# stepper_driver.net
KiCad netlist of a schematic drawn in EAGLE
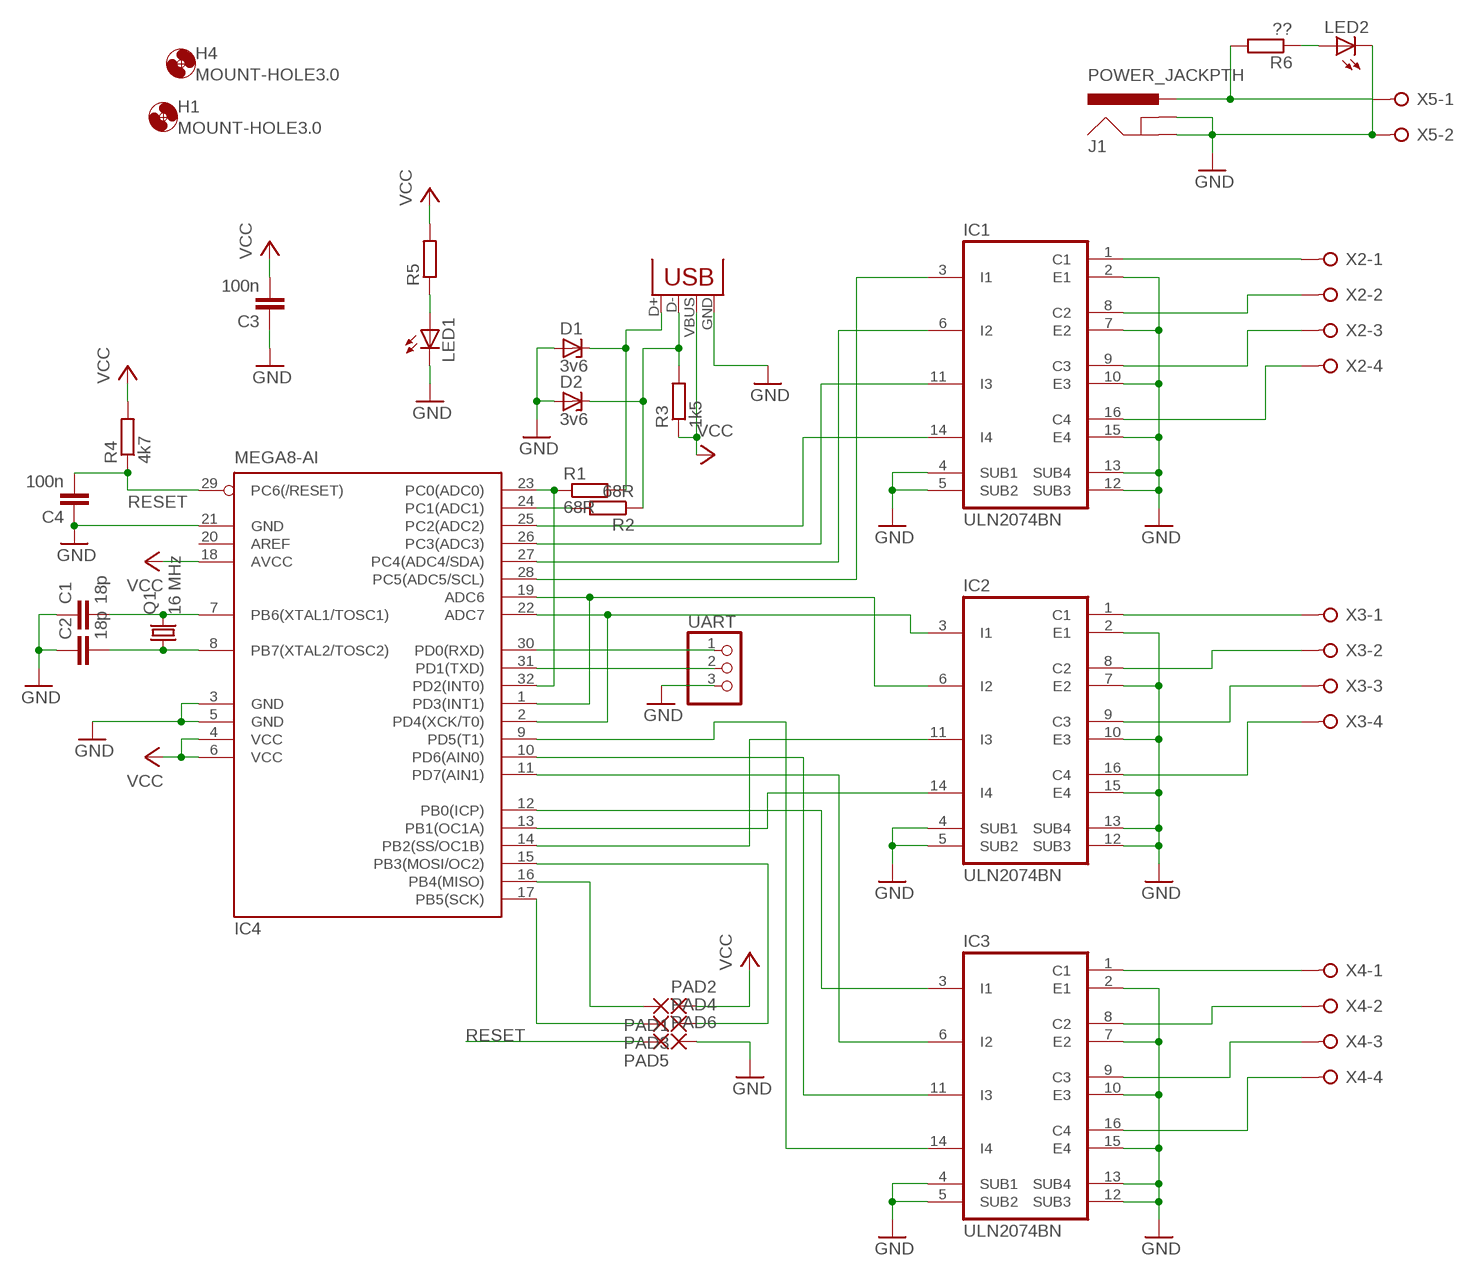
[diagram p0: schematic, sheet 1]

(export (version "E")
  (design (tool "Eeschema 10.0.6"))
  (components
    (comp (ref "C1")
      (value "18p")
      (footprint "eagle-import:C025-025X050")
      (libsource (lib "eagle-import") (part "C-EU025-025X050"))
    )
    (comp (ref "C2")
      (value "18p")
      (footprint "eagle-import:C025-025X050")
      (libsource (lib "eagle-import") (part "C-EU025-025X050"))
    )
    (comp (ref "C3")
      (value "100n")
      (footprint "eagle-import:C025-025X050")
      (libsource (lib "eagle-import") (part "C-EU025-025X050"))
    )
    (comp (ref "C4")
      (value "100n")
      (footprint "eagle-import:C025-025X050")
      (libsource (lib "eagle-import") (part "C-EU025-025X050"))
    )
    (comp (ref "D1")
      (value "3v6")
      (footprint "eagle-import:DO35Z10")
      (libsource (lib "eagle-import") (part "ZENER-DIODEDO35Z10"))
    )
    (comp (ref "D2")
      (value "3v6")
      (footprint "eagle-import:DO35Z10")
      (libsource (lib "eagle-import") (part "ZENER-DIODEDO35Z10"))
    )
    (comp (ref "H1")
      (value "MOUNT-HOLE3.0")
      (footprint "eagle-import:3,0")
      (libsource (lib "eagle-import") (part "MOUNT-HOLE3.0"))
    )
    (comp (ref "H4")
      (value "MOUNT-HOLE3.0")
      (footprint "eagle-import:3,0")
      (libsource (lib "eagle-import") (part "MOUNT-HOLE3.0"))
    )
    (comp (ref "IC1")
      (value "ULN2074BN")
      (footprint "eagle-import:DIL16")
      (libsource (lib "eagle-import") (part "ULN2074BN"))
    )
    (comp (ref "IC2")
      (value "ULN2074BN")
      (footprint "eagle-import:DIL16")
      (libsource (lib "eagle-import") (part "ULN2074BN"))
    )
    (comp (ref "IC3")
      (value "ULN2074BN")
      (footprint "eagle-import:DIL16")
      (libsource (lib "eagle-import") (part "ULN2074BN"))
    )
    (comp (ref "IC4")
      (value "MEGA8-AI")
      (footprint "eagle-import:TQFP32-08")
      (fields (field (name "MPN") "ATMEGA8-16AU"))
      (libsource (lib "eagle-import") (part "MEGA8-AI"))
    )
    (comp (ref "J1")
      (value "POWER_JACKPTH")
      (footprint "eagle-import:POWER_JACK_PTH")
      (libsource (lib "eagle-import") (part "POWER_JACKPTH"))
    )
    (comp (ref "LED1")
      (value "LED3MM")
      (footprint "eagle-import:LED3MM")
      (libsource (lib "eagle-import") (part "LED3MM"))
    )
    (comp (ref "LED2")
      (value "LED3MM")
      (footprint "eagle-import:LED3MM")
      (libsource (lib "eagle-import") (part "LED3MM"))
    )
    (comp (ref "PAD1")
      (value "2,15/1,0")
      (footprint "eagle-import:2,15_1,0")
      (libsource (lib "eagle-import") (part "2,15/1,0"))
    )
    (comp (ref "PAD2")
      (value "2,15/1,0")
      (footprint "eagle-import:2,15_1,0")
      (libsource (lib "eagle-import") (part "2,15/1,0"))
    )
    (comp (ref "PAD3")
      (value "2,15/1,0")
      (footprint "eagle-import:2,15_1,0")
      (libsource (lib "eagle-import") (part "2,15/1,0"))
    )
    (comp (ref "PAD4")
      (value "2,15/1,0")
      (footprint "eagle-import:2,15_1,0")
      (libsource (lib "eagle-import") (part "2,15/1,0"))
    )
    (comp (ref "PAD5")
      (value "2,15/1,0")
      (footprint "eagle-import:2,15_1,0")
      (libsource (lib "eagle-import") (part "2,15/1,0"))
    )
    (comp (ref "PAD6")
      (value "2,15/1,0")
      (footprint "eagle-import:2,15_1,0")
      (libsource (lib "eagle-import") (part "2,15/1,0"))
    )
    (comp (ref "Q1")
      (value "16 MHz")
      (footprint "eagle-import:HC49_S")
      (libsource (lib "eagle-import") (part "CRYSTALHC49S"))
    )
    (comp (ref "R1")
      (value "68R")
      (footprint "eagle-import:0207_10")
      (libsource (lib "eagle-import") (part "R-EU_0207/10"))
    )
    (comp (ref "R2")
      (value "68R")
      (footprint "eagle-import:0207_10")
      (libsource (lib "eagle-import") (part "R-EU_0207/10"))
    )
    (comp (ref "R3")
      (value "1k5")
      (footprint "eagle-import:0207_10")
      (libsource (lib "eagle-import") (part "R-EU_0207/10"))
    )
    (comp (ref "R4")
      (value "4k7")
      (footprint "eagle-import:0207_10")
      (libsource (lib "eagle-import") (part "R-EU_0207/10"))
    )
    (comp (ref "R5")
      (value "R-EU_0207/10")
      (footprint "eagle-import:0207_10")
      (libsource (lib "eagle-import") (part "R-EU_0207/10"))
    )
    (comp (ref "R6")
      (value "??")
      (footprint "eagle-import:0207_10")
      (libsource (lib "eagle-import") (part "R-EU_0207/10"))
    )
    (comp (ref "UART")
      (value "PINHD-1X3")
      (footprint "eagle-import:1X03")
      (libsource (lib "eagle-import") (part "PINHD-1X3"))
    )
    (comp (ref "X1")
      (value "USBPTH")
      (footprint "eagle-import:USB-B-PTH")
      (libsource (lib "eagle-import") (part "USBPTH"))
    )
    (comp (ref "X2")
      (value "W237-04P")
      (footprint "eagle-import:W237-4P")
      (libsource (lib "eagle-import") (part "W237-04P"))
    )
    (comp (ref "X3")
      (value "W237-04P")
      (footprint "eagle-import:W237-4P")
      (libsource (lib "eagle-import") (part "W237-04P"))
    )
    (comp (ref "X4")
      (value "W237-04P")
      (footprint "eagle-import:W237-4P")
      (libsource (lib "eagle-import") (part "W237-04P"))
    )
    (comp (ref "X5")
      (value "W237-02P")
      (footprint "eagle-import:W237-132")
      (libsource (lib "eagle-import") (part "W237-02P"))
    )
  )
  (nets
    (net (code "1") (name "/RESET") (class "Default")
      (node (ref "C4") (pin "2") (pinfunction "2_2") (pintype "passive"))
      (node (ref "IC4") (pin "29") (pinfunction "PC6(/RESET)_29") (pintype "bidirectional"))
      (node (ref "PAD5") (pin "1") (pinfunction "P_1") (pintype "passive"))
      (node (ref "R4") (pin "1") (pinfunction "1_1") (pintype "passive"))
    )
    (net (code "2") (name "GND") (class "Default")
      (node (ref "C1") (pin "1") (pinfunction "1_1") (pintype "passive"))
      (node (ref "C2") (pin "1") (pinfunction "1_1") (pintype "passive"))
      (node (ref "C3") (pin "1") (pinfunction "1_1") (pintype "passive"))
      (node (ref "C4") (pin "1") (pinfunction "1_1") (pintype "passive"))
      (node (ref "D1") (pin "A") (pinfunction "A_A") (pintype "passive"))
      (node (ref "D2") (pin "A") (pinfunction "A_A") (pintype "passive"))
      (node (ref "IC1") (pin "10") (pinfunction "E3_10") (pintype "open_collector"))
      (node (ref "IC1") (pin "12") (pinfunction "SUB3_12") (pintype "passive"))
      (node (ref "IC1") (pin "13") (pinfunction "SUB4_13") (pintype "passive"))
      (node (ref "IC1") (pin "15") (pinfunction "E4_15") (pintype "open_collector"))
      (node (ref "IC1") (pin "2") (pinfunction "E1_2") (pintype "open_collector"))
      (node (ref "IC1") (pin "4") (pinfunction "SUB1_4") (pintype "passive"))
      (node (ref "IC1") (pin "5") (pinfunction "SUB2_5") (pintype "passive"))
      (node (ref "IC1") (pin "7") (pinfunction "E2_7") (pintype "open_collector"))
      (node (ref "IC2") (pin "10") (pinfunction "E3_10") (pintype "open_collector"))
      (node (ref "IC2") (pin "12") (pinfunction "SUB3_12") (pintype "passive"))
      (node (ref "IC2") (pin "13") (pinfunction "SUB4_13") (pintype "passive"))
      (node (ref "IC2") (pin "15") (pinfunction "E4_15") (pintype "open_collector"))
      (node (ref "IC2") (pin "2") (pinfunction "E1_2") (pintype "open_collector"))
      (node (ref "IC2") (pin "4") (pinfunction "SUB1_4") (pintype "passive"))
      (node (ref "IC2") (pin "5") (pinfunction "SUB2_5") (pintype "passive"))
      (node (ref "IC2") (pin "7") (pinfunction "E2_7") (pintype "open_collector"))
      (node (ref "IC3") (pin "10") (pinfunction "E3_10") (pintype "open_collector"))
      (node (ref "IC3") (pin "12") (pinfunction "SUB3_12") (pintype "passive"))
      (node (ref "IC3") (pin "13") (pinfunction "SUB4_13") (pintype "passive"))
      (node (ref "IC3") (pin "15") (pinfunction "E4_15") (pintype "open_collector"))
      (node (ref "IC3") (pin "2") (pinfunction "E1_2") (pintype "open_collector"))
      (node (ref "IC3") (pin "4") (pinfunction "SUB1_4") (pintype "passive"))
      (node (ref "IC3") (pin "5") (pinfunction "SUB2_5") (pintype "passive"))
      (node (ref "IC3") (pin "7") (pinfunction "E2_7") (pintype "open_collector"))
      (node (ref "IC4") (pin "21") (pinfunction "GND_21") (pintype "power_in"))
      (node (ref "IC4") (pin "3") (pinfunction "GND_3") (pintype "power_in"))
      (node (ref "IC4") (pin "5") (pinfunction "GND_5") (pintype "power_in"))
      (node (ref "J1") (pin "GND") (pinfunction "GND_GND") (pintype "bidirectional"))
      (node (ref "J1") (pin "GNDBREAK") (pinfunction "GNDBREAK_GNDBREAK") (pintype "bidirectional"))
      (node (ref "LED1") (pin "K") (pinfunction "C_K") (pintype "passive"))
      (node (ref "LED2") (pin "K") (pinfunction "C_K") (pintype "passive"))
      (node (ref "PAD6") (pin "1") (pinfunction "P_1") (pintype "passive"))
      (node (ref "UART") (pin "3") (pinfunction "3_3") (pintype "passive"))
      (node (ref "X1") (pin "GND") (pinfunction "GND_GND") (pintype "bidirectional"))
      (node (ref "X5") (pin "2") (pinfunction "KL_2") (pintype "passive"))
    )
    (net (code "3") (name "Net-(D1-PadC)") (class "Default")
      (node (ref "D1") (pin "C") (pinfunction "C_C") (pintype "passive"))
      (node (ref "R1") (pin "2") (pinfunction "2_2") (pintype "passive"))
      (node (ref "X1") (pin "D+") (pinfunction "D+_D+") (pintype "bidirectional"))
    )
    (net (code "4") (name "Net-(D2-PadC)") (class "Default")
      (node (ref "D2") (pin "C") (pinfunction "C_C") (pintype "passive"))
      (node (ref "R2") (pin "1") (pinfunction "1_1") (pintype "passive"))
      (node (ref "R3") (pin "2") (pinfunction "2_2") (pintype "passive"))
      (node (ref "X1") (pin "D-") (pinfunction "D-_D-") (pintype "bidirectional"))
    )
    (net (code "5") (name "Net-(IC1-C1)") (class "Default")
      (node (ref "IC1") (pin "1") (pinfunction "C1_1") (pintype "open_collector"))
      (node (ref "X2") (pin "1") (pinfunction "KL_1") (pintype "passive"))
    )
    (net (code "6") (name "Net-(IC1-C2)") (class "Default")
      (node (ref "IC1") (pin "8") (pinfunction "C2_8") (pintype "open_collector"))
      (node (ref "X2") (pin "2") (pinfunction "KL_2") (pintype "passive"))
    )
    (net (code "7") (name "Net-(IC1-C3)") (class "Default")
      (node (ref "IC1") (pin "9") (pinfunction "C3_9") (pintype "open_collector"))
      (node (ref "X2") (pin "3") (pinfunction "KL_3") (pintype "passive"))
    )
    (net (code "8") (name "Net-(IC1-C4)") (class "Default")
      (node (ref "IC1") (pin "16") (pinfunction "C4_16") (pintype "open_collector"))
      (node (ref "X2") (pin "4") (pinfunction "KL_4") (pintype "passive"))
    )
    (net (code "9") (name "Net-(IC1-I1)") (class "Default")
      (node (ref "IC1") (pin "3") (pinfunction "I1_3") (pintype "input"))
      (node (ref "IC4") (pin "28") (pinfunction "PC5(ADC5/SCL)_28") (pintype "bidirectional"))
    )
    (net (code "10") (name "Net-(IC1-I2)") (class "Default")
      (node (ref "IC1") (pin "6") (pinfunction "I2_6") (pintype "input"))
      (node (ref "IC4") (pin "27") (pinfunction "PC4(ADC4/SDA)_27") (pintype "bidirectional"))
    )
    (net (code "11") (name "Net-(IC1-I3)") (class "Default")
      (node (ref "IC1") (pin "11") (pinfunction "I3_11") (pintype "input"))
      (node (ref "IC4") (pin "26") (pinfunction "PC3(ADC3)_26") (pintype "bidirectional"))
    )
    (net (code "12") (name "Net-(IC1-I4)") (class "Default")
      (node (ref "IC1") (pin "14") (pinfunction "I4_14") (pintype "input"))
      (node (ref "IC4") (pin "25") (pinfunction "PC2(ADC2)_25") (pintype "bidirectional"))
    )
    (net (code "13") (name "Net-(IC2-C1)") (class "Default")
      (node (ref "IC2") (pin "1") (pinfunction "C1_1") (pintype "open_collector"))
      (node (ref "X3") (pin "1") (pinfunction "KL_1") (pintype "passive"))
    )
    (net (code "14") (name "Net-(IC2-C2)") (class "Default")
      (node (ref "IC2") (pin "8") (pinfunction "C2_8") (pintype "open_collector"))
      (node (ref "X3") (pin "2") (pinfunction "KL_2") (pintype "passive"))
    )
    (net (code "15") (name "Net-(IC2-C3)") (class "Default")
      (node (ref "IC2") (pin "9") (pinfunction "C3_9") (pintype "open_collector"))
      (node (ref "X3") (pin "3") (pinfunction "KL_3") (pintype "passive"))
    )
    (net (code "16") (name "Net-(IC2-C4)") (class "Default")
      (node (ref "IC2") (pin "16") (pinfunction "C4_16") (pintype "open_collector"))
      (node (ref "X3") (pin "4") (pinfunction "KL_4") (pintype "passive"))
    )
    (net (code "17") (name "Net-(IC2-I1)") (class "Default")
      (node (ref "IC2") (pin "3") (pinfunction "I1_3") (pintype "input"))
      (node (ref "IC4") (pin "2") (pinfunction "PD4(XCK/T0)_2") (pintype "bidirectional"))
      (node (ref "IC4") (pin "22") (pinfunction "ADC7_22") (pintype "bidirectional"))
    )
    (net (code "18") (name "Net-(IC2-I2)") (class "Default")
      (node (ref "IC2") (pin "6") (pinfunction "I2_6") (pintype "input"))
      (node (ref "IC4") (pin "1") (pinfunction "PD3(INT1)_1") (pintype "bidirectional"))
      (node (ref "IC4") (pin "19") (pinfunction "ADC6_19") (pintype "bidirectional"))
    )
    (net (code "19") (name "Net-(IC2-I3)") (class "Default")
      (node (ref "IC2") (pin "11") (pinfunction "I3_11") (pintype "input"))
      (node (ref "IC4") (pin "14") (pinfunction "PB2(SS/OC1B)_14") (pintype "bidirectional"))
    )
    (net (code "20") (name "Net-(IC2-I4)") (class "Default")
      (node (ref "IC2") (pin "14") (pinfunction "I4_14") (pintype "input"))
      (node (ref "IC4") (pin "13") (pinfunction "PB1(OC1A)_13") (pintype "bidirectional"))
    )
    (net (code "21") (name "Net-(IC3-C1)") (class "Default")
      (node (ref "IC3") (pin "1") (pinfunction "C1_1") (pintype "open_collector"))
      (node (ref "X4") (pin "1") (pinfunction "KL_1") (pintype "passive"))
    )
    (net (code "22") (name "Net-(IC3-C2)") (class "Default")
      (node (ref "IC3") (pin "8") (pinfunction "C2_8") (pintype "open_collector"))
      (node (ref "X4") (pin "2") (pinfunction "KL_2") (pintype "passive"))
    )
    (net (code "23") (name "Net-(IC3-C3)") (class "Default")
      (node (ref "IC3") (pin "9") (pinfunction "C3_9") (pintype "open_collector"))
      (node (ref "X4") (pin "3") (pinfunction "KL_3") (pintype "passive"))
    )
    (net (code "24") (name "Net-(IC3-C4)") (class "Default")
      (node (ref "IC3") (pin "16") (pinfunction "C4_16") (pintype "open_collector"))
      (node (ref "X4") (pin "4") (pinfunction "KL_4") (pintype "passive"))
    )
    (net (code "25") (name "Net-(IC3-I1)") (class "Default")
      (node (ref "IC3") (pin "3") (pinfunction "I1_3") (pintype "input"))
      (node (ref "IC4") (pin "12") (pinfunction "PB0(ICP)_12") (pintype "bidirectional"))
    )
    (net (code "26") (name "Net-(IC3-I2)") (class "Default")
      (node (ref "IC3") (pin "6") (pinfunction "I2_6") (pintype "input"))
      (node (ref "IC4") (pin "11") (pinfunction "PD7(AIN1)_11") (pintype "bidirectional"))
    )
    (net (code "27") (name "Net-(IC3-I3)") (class "Default")
      (node (ref "IC3") (pin "11") (pinfunction "I3_11") (pintype "input"))
      (node (ref "IC4") (pin "10") (pinfunction "PD6(AIN0)_10") (pintype "bidirectional"))
    )
    (net (code "28") (name "Net-(IC3-I4)") (class "Default")
      (node (ref "IC3") (pin "14") (pinfunction "I4_14") (pintype "input"))
      (node (ref "IC4") (pin "9") (pinfunction "PD5(T1)_9") (pintype "bidirectional"))
    )
    (net (code "29") (name "Net-(IC4-PB3(MOSI{slash}OC2))") (class "Default")
      (node (ref "IC4") (pin "15") (pinfunction "PB3(MOSI/OC2)_15") (pintype "bidirectional"))
      (node (ref "PAD4") (pin "1") (pinfunction "P_1") (pintype "passive"))
    )
    (net (code "30") (name "Net-(IC4-PB4(MISO))") (class "Default")
      (node (ref "IC4") (pin "16") (pinfunction "PB4(MISO)_16") (pintype "bidirectional"))
      (node (ref "PAD1") (pin "1") (pinfunction "P_1") (pintype "passive"))
    )
    (net (code "31") (name "Net-(IC4-PB5(SCK))") (class "Default")
      (node (ref "IC4") (pin "17") (pinfunction "PB5(SCK)_17") (pintype "bidirectional"))
      (node (ref "PAD3") (pin "1") (pinfunction "P_1") (pintype "passive"))
    )
    (net (code "32") (name "Net-(IC4-PB6(XTAL1{slash}TOSC1))") (class "Default")
      (node (ref "C1") (pin "2") (pinfunction "2_2") (pintype "passive"))
      (node (ref "IC4") (pin "7") (pinfunction "PB6(XTAL1/TOSC1)_7") (pintype "bidirectional"))
      (node (ref "Q1") (pin "2") (pinfunction "2_2") (pintype "passive"))
    )
    (net (code "33") (name "Net-(IC4-PB7(XTAL2{slash}TOSC2))") (class "Default")
      (node (ref "C2") (pin "2") (pinfunction "2_2") (pintype "passive"))
      (node (ref "IC4") (pin "8") (pinfunction "PB7(XTAL2/TOSC2)_8") (pintype "bidirectional"))
      (node (ref "Q1") (pin "1") (pinfunction "1_1") (pintype "passive"))
    )
    (net (code "34") (name "Net-(IC4-PC0(ADC0))") (class "Default")
      (node (ref "IC4") (pin "23") (pinfunction "PC0(ADC0)_23") (pintype "bidirectional"))
      (node (ref "IC4") (pin "32") (pinfunction "PD2(INT0)_32") (pintype "bidirectional"))
      (node (ref "R1") (pin "1") (pinfunction "1_1") (pintype "passive"))
    )
    (net (code "35") (name "Net-(IC4-PC1(ADC1))") (class "Default")
      (node (ref "IC4") (pin "24") (pinfunction "PC1(ADC1)_24") (pintype "bidirectional"))
      (node (ref "R2") (pin "2") (pinfunction "2_2") (pintype "passive"))
    )
    (net (code "36") (name "Net-(IC4-PD0(RXD))") (class "Default")
      (node (ref "IC4") (pin "30") (pinfunction "PD0(RXD)_30") (pintype "bidirectional"))
      (node (ref "UART") (pin "1") (pinfunction "1_1") (pintype "passive"))
    )
    (net (code "37") (name "Net-(IC4-PD1(TXD))") (class "Default")
      (node (ref "IC4") (pin "31") (pinfunction "PD1(TXD)_31") (pintype "bidirectional"))
      (node (ref "UART") (pin "2") (pinfunction "2_2") (pintype "passive"))
    )
    (net (code "38") (name "Net-(LED1-PadA)") (class "Default")
      (node (ref "LED1") (pin "A") (pinfunction "A_A") (pintype "passive"))
      (node (ref "R5") (pin "1") (pinfunction "1_1") (pintype "passive"))
    )
    (net (code "39") (name "Net-(LED2-PadA)") (class "Default")
      (node (ref "LED2") (pin "A") (pinfunction "A_A") (pintype "passive"))
      (node (ref "R6") (pin "1") (pinfunction "1_1") (pintype "passive"))
    )
    (net (code "40") (name "Net-(X5A-KL)") (class "Default")
      (node (ref "J1") (pin "PWR") (pinfunction "PWR_PWR") (pintype "bidirectional"))
      (node (ref "R6") (pin "2") (pinfunction "2_2") (pintype "passive"))
      (node (ref "X5") (pin "1") (pinfunction "KL_1") (pintype "passive"))
    )
    (net (code "41") (name "VCC") (class "Default")
      (node (ref "C3") (pin "2") (pinfunction "2_2") (pintype "passive"))
      (node (ref "IC4") (pin "18") (pinfunction "AVCC_18") (pintype "power_in"))
      (node (ref "IC4") (pin "4") (pinfunction "VCC_4") (pintype "power_in"))
      (node (ref "IC4") (pin "6") (pinfunction "VCC_6") (pintype "power_in"))
      (node (ref "PAD2") (pin "1") (pinfunction "P_1") (pintype "passive"))
      (node (ref "R3") (pin "1") (pinfunction "1_1") (pintype "passive"))
      (node (ref "R4") (pin "2") (pinfunction "2_2") (pintype "passive"))
      (node (ref "R5") (pin "2") (pinfunction "2_2") (pintype "passive"))
      (node (ref "X1") (pin "VBUS") (pinfunction "VBUS_VBUS") (pintype "bidirectional"))
    )
    (net (code "42") (name "unconnected-(IC4-AREF-Pad20)") (class "Default")
      (node (ref "IC4") (pin "20") (pinfunction "AREF_20") (pintype "passive"))
    )
  )
)
